# Sheet1.net
KiCad netlist of a schematic drawn in Altium Designer
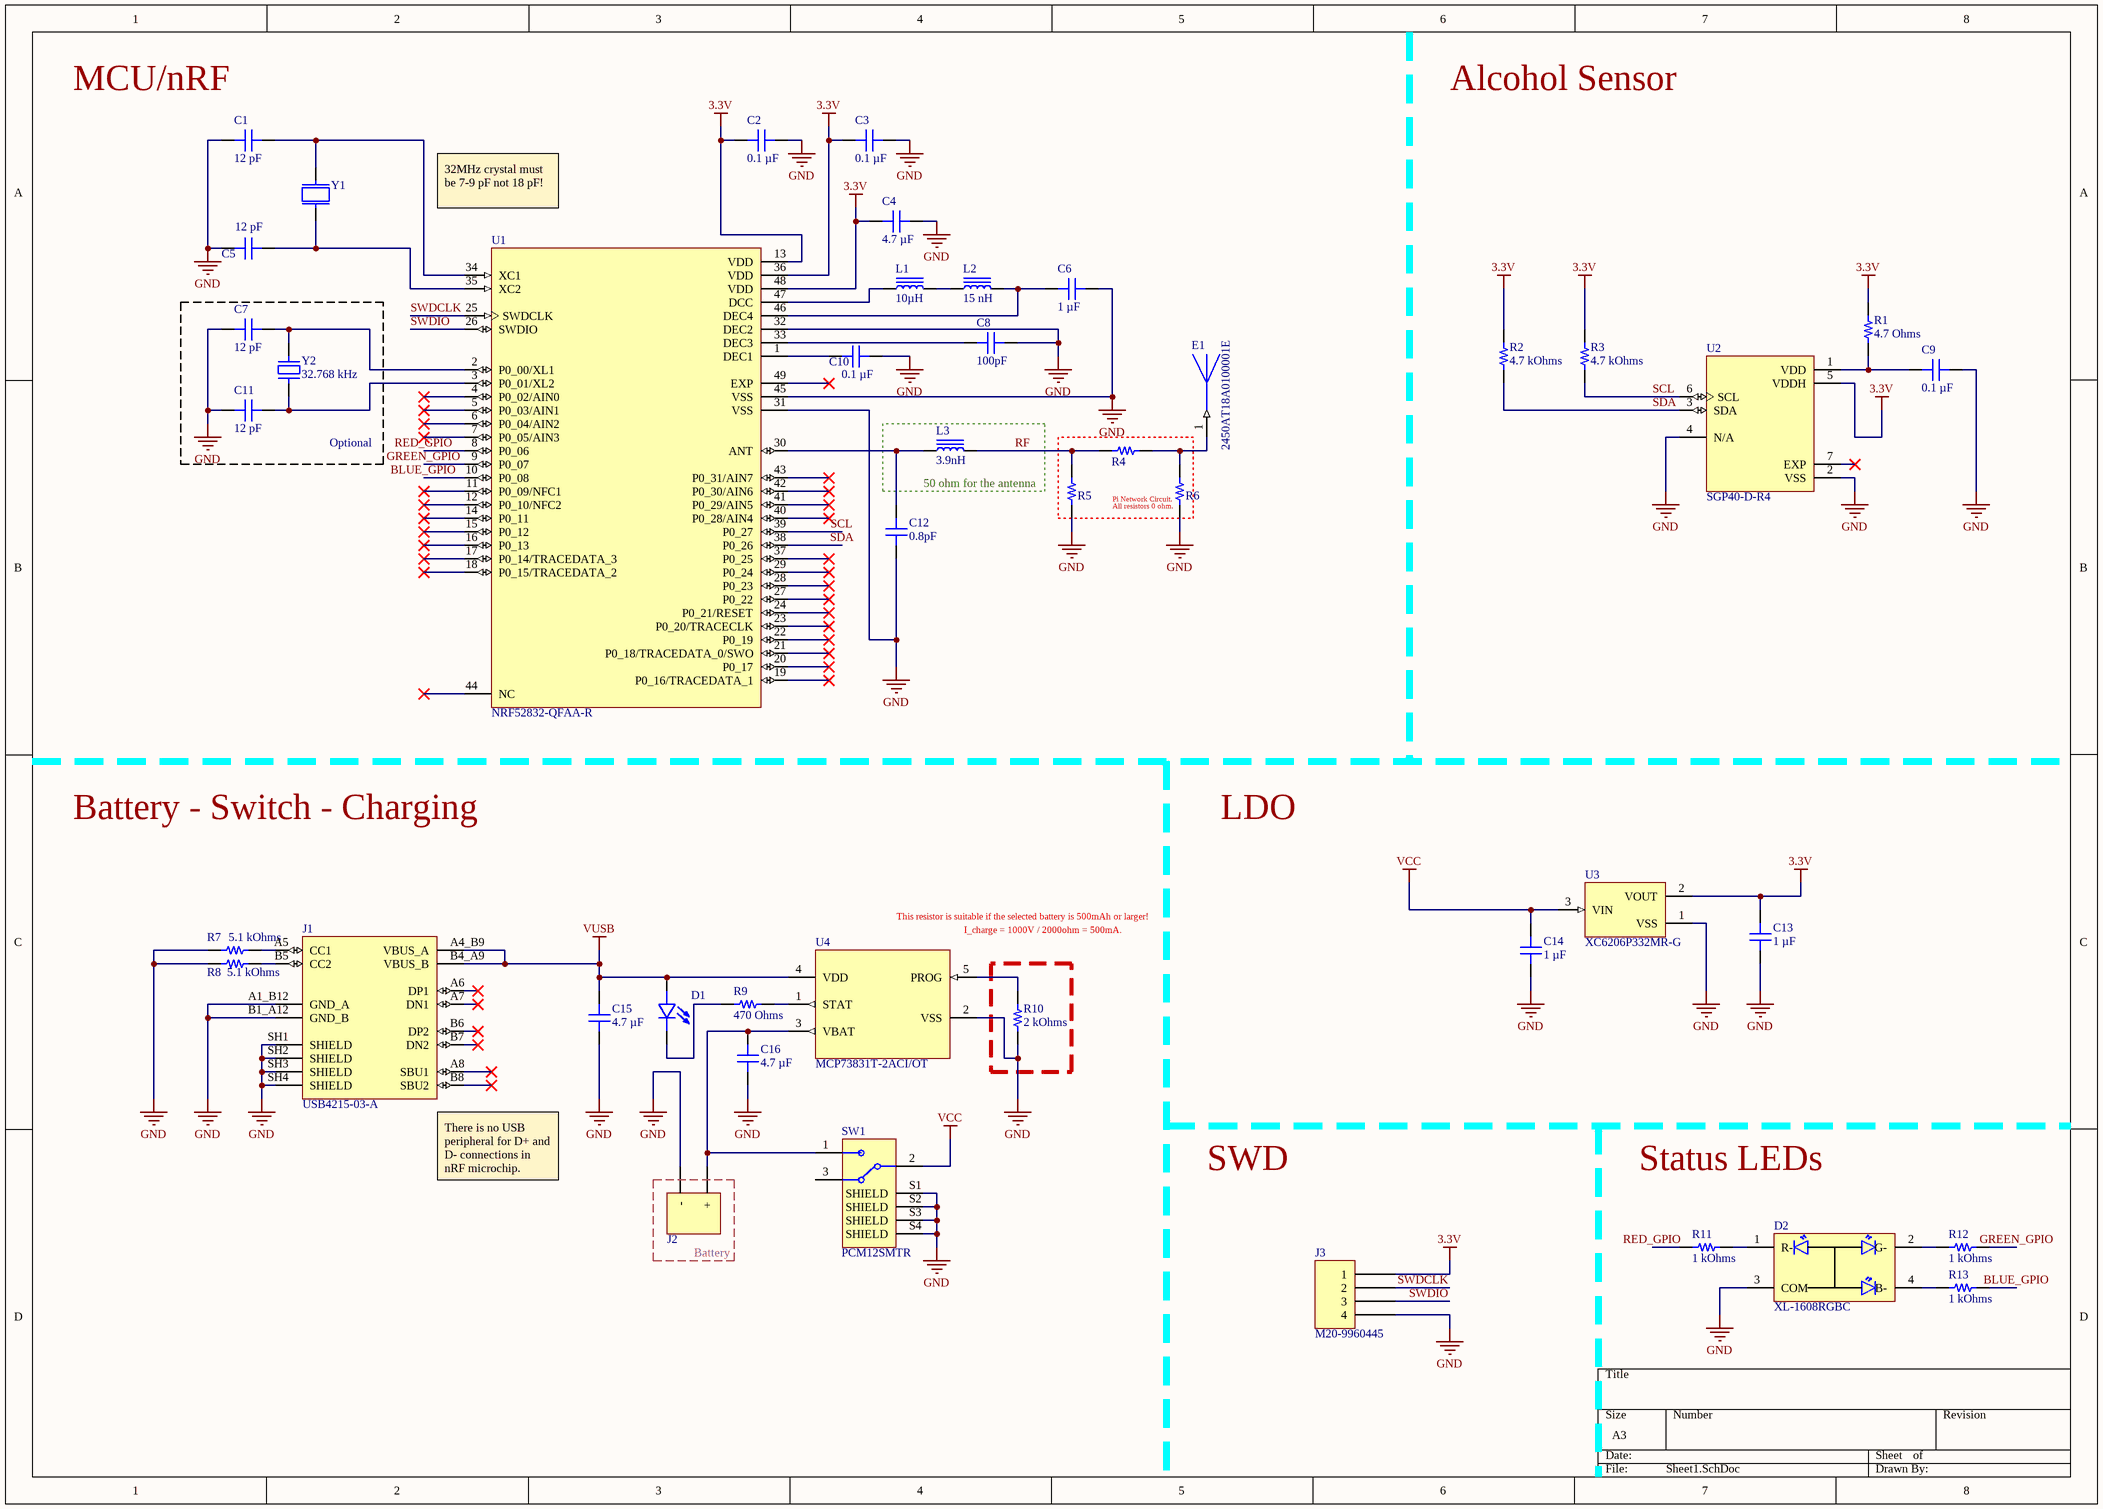
[diagram p0: Sheet1.SchDoc]

(export (version "E")
  (design (tool "Eeschema 10.0.6"))
  (components
    (comp (ref "C1")
      (value "12 pF")
      (footprint "CAP 0402_1005")
      (description "CAP CER 12PF 50V C0G/NP0 0402")
      (fields (field (name "PART NUMBER") "CBR04C120F5GAC") (field (name "MANUFACTURER") "KEMET"))
      (libsource (lib "Celestial Altium Library - altium_library") (part "Capacitor"))
    )
    (comp (ref "C2")
      (value "0.1 µF")
      (footprint "CAP 0402_1005")
      (description "CAP CER 100NF 10V X7R 0402")
      (fields
        (field (name "PART NUMBER") "CL05B104KP5VPNC")
        (field (name "MANUFACTURER") "Samsung Electro-Mechanics")
      )
      (libsource (lib "Celestial Altium Library - altium_library") (part "Capacitor"))
    )
    (comp (ref "C3")
      (value "0.1 µF")
      (footprint "CAP 0402_1005")
      (description "CAP CER 100NF 10V X7R 0402")
      (fields
        (field (name "PART NUMBER") "CL05B104KP5VPNC")
        (field (name "MANUFACTURER") "Samsung Electro-Mechanics")
      )
      (libsource (lib "Celestial Altium Library - altium_library") (part "Capacitor"))
    )
    (comp (ref "C4")
      (value "4.7 µF")
      (footprint "CAP 0402_1005")
      (description "CAP CER 4.7UF 16V X5R 0402")
      (fields
        (field (name "PART NUMBER") "CL05A475MO5NUNC")
        (field (name "MANUFACTURER") "Samsung Electro-Mechanics")
      )
      (libsource (lib "Celestial Altium Library - altium_library") (part "Capacitor"))
    )
    (comp (ref "C5")
      (value "12 pF")
      (footprint "CAP 0402_1005")
      (description "CAP CER 12PF 50V C0G/NP0 0402")
      (fields (field (name "PART NUMBER") "CBR04C120F5GAC") (field (name "MANUFACTURER") "KEMET"))
      (libsource (lib "Celestial Altium Library - altium_library") (part "Capacitor"))
    )
    (comp (ref "C6")
      (value "1 µF")
      (footprint "CAP 0402_1005")
      (description "CAP CER 1UF 10V X5R 0402")
      (fields (field (name "PART NUMBER") "885012105012") (field (name "MANUFACTURER") "Würth Elektronik"))
      (libsource (lib "Celestial Altium Library - altium_library") (part "Capacitor"))
    )
    (comp (ref "C7")
      (value "12 pF")
      (footprint "CAP 0402_1005")
      (description "CAP CER 12PF 25V NP0 0402")
      (fields (field (name "PART NUMBER") "C0402C120J3GAC7867") (field (name "MANUFACTURER") "KEMET"))
      (libsource (lib "Celestial Altium Library - altium_library") (part "Capacitor"))
    )
    (comp (ref "C8")
      (value "100pF")
      (footprint "CAP 0402_1005")
      (description "CAP CER 100PF 10V X7R 0402")
      (fields (field (name "PART NUMBER") "0402ZC101MAT2A") (field (name "MANUFACTURER") "AVX Corporation"))
      (libsource (lib "Celestial Altium Library - altium_library") (part "Capacitor"))
    )
    (comp (ref "C9")
      (value "0.1 µF")
      (footprint "CAP 0402_1005")
      (description "CAP CER 100NF 10V X7R 0402")
      (fields
        (field (name "PART NUMBER") "CL05B104KP5VPNC")
        (field (name "MANUFACTURER") "Samsung Electro-Mechanics")
      )
      (libsource (lib "Celestial Altium Library - altium_library") (part "Capacitor"))
    )
    (comp (ref "C10")
      (value "0.1 µF")
      (footprint "CAP 0402_1005")
      (description "CAP CER 100NF 10V X7R 0402")
      (fields
        (field (name "PART NUMBER") "CL05B104KP5VPNC")
        (field (name "MANUFACTURER") "Samsung Electro-Mechanics")
      )
      (libsource (lib "Celestial Altium Library - altium_library") (part "Capacitor"))
    )
    (comp (ref "C11")
      (value "12 pF")
      (footprint "CAP 0402_1005")
      (description "CAP CER 12PF 25V NP0 0402")
      (fields (field (name "PART NUMBER") "C0402C120J3GAC7867") (field (name "MANUFACTURER") "KEMET"))
      (libsource (lib "Celestial Altium Library - altium_library") (part "Capacitor"))
    )
    (comp (ref "C12")
      (value "0.8pF")
      (footprint "CAP 0402_1005")
      (description "CAP CER 0.8PF 50V NP0 0402")
      (fields (field (name "PART NUMBER") "04025A0R8BAT2A") (field (name "MANUFACTURER") "AVX Corporation"))
      (libsource (lib "Celestial Altium Library - altium_library") (part "Capacitor"))
    )
    (comp (ref "C13")
      (value "1 µF")
      (footprint "CAP 0402_1005")
      (description "CAP CER 1UF 10V X5R 0402")
      (fields (field (name "PART NUMBER") "885012105012") (field (name "MANUFACTURER") "Würth Elektronik"))
      (libsource (lib "Celestial Altium Library - altium_library") (part "Capacitor"))
    )
    (comp (ref "C14")
      (value "1 µF")
      (footprint "CAP 0402_1005")
      (description "CAP CER 1UF 10V X5R 0402")
      (fields (field (name "PART NUMBER") "885012105012") (field (name "MANUFACTURER") "Würth Elektronik"))
      (libsource (lib "Celestial Altium Library - altium_library") (part "Capacitor"))
    )
    (comp (ref "C15")
      (value "4.7 µF")
      (footprint "CAP 0402_1005")
      (description "CAP CER 4.7UF 16V X5R 0402")
      (fields
        (field (name "PART NUMBER") "CL05A475MO5NUNC")
        (field (name "MANUFACTURER") "Samsung Electro-Mechanics")
      )
      (libsource (lib "Celestial Altium Library - altium_library") (part "Capacitor"))
    )
    (comp (ref "C16")
      (value "4.7 µF")
      (footprint "CAP 0402_1005")
      (description "CAP CER 4.7UF 16V X5R 0402")
      (fields
        (field (name "PART NUMBER") "CL05A475MO5NUNC")
        (field (name "MANUFACTURER") "Samsung Electro-Mechanics")
      )
      (libsource (lib "Celestial Altium Library - altium_library") (part "Capacitor"))
    )
    (comp (ref "D1")
      (value "XZFBB53W-1")
      (footprint "XZFBB53W-1")
      (description "1.6X0.8MM BLUE SMD 0603 LED")
      (libsource (lib "Schlib1") (part "XZFBB53W-1"))
    )
    (comp (ref "D2")
      (value "XL-1608RGBC")
      (footprint "XL-1608RGBC")
      (libsource (lib "Schlib1") (part "XL-1608RGBC"))
    )
    (comp (ref "E1")
      (value "2450AT18A0100001E")
      (footprint "2450AT18A0100001E")
      (description "2.4GHz Chip RF Antenna 2.4GHz ~ 2.5GHz 0.5dBi Solder Surface Mount")
      (libsource (lib "Schlib1") (part "2450AT18A0100001E"))
    )
    (comp (ref "J1")
      (value "USB4215-03-A")
      (footprint "USB4215-03-A")
      (libsource (lib "Schlib1") (part "USB4215-03-A"))
    )
    (comp (ref "J2")
      (value "Male Header 2 Pin")
      (footprint "Male Header 2 Pin")
      (libsource (lib "Schlib1") (part "Male Header 2 Pin"))
    )
    (comp (ref "J3")
      (value "M20-9960445")
      (footprint "HARWIN M20-9960445")
      (description "CONN HEADER R/A 4POS 2.54MM")
      (fields (field (name "MANUFACTURER") "Harwin Inc."))
      (libsource (lib "Celestial Altium Library - altium_library") (part "4 Pin"))
    )
    (comp (ref "L1")
      (value "10µH")
      (footprint "IND 1008_2520")
      (description "FIXED IND 10UH 850MA 300 MOHM")
      (fields (field (name "PART NUMBER") "74479887310A") (field (name "MANUFACTURER") "Würth Elektronik"))
      (libsource (lib "Celestial Altium Library - altium_library") (part "Inductor"))
    )
    (comp (ref "L2")
      (value "15 nH")
      (footprint "IND 0201_0603")
      (description "FIXED IND 15NH 300MA 700MOHM SMD")
      (fields
        (field (name "PART NUMBER") "LQP03HQ15NJ02D")
        (field (name "MANUFACTURER") "Murata Electronics")
      )
      (libsource (lib "Celestial Altium Library - altium_library") (part "Inductor"))
    )
    (comp (ref "L3")
      (value "3.9nH")
      (footprint "IND 0402_1005")
      (description "RF INDUCTOR ML")
      (fields
        (field (name "PART NUMBER") "BSCH001005053N9SCP")
        (field (name "MANUFACTURER") "Chilisin Electronics")
      )
      (libsource (lib "Celestial Altium Library - altium_library") (part "Inductor"))
    )
    (comp (ref "R1")
      (value "4.7 Ohms")
      (footprint "RES 0402_1005")
      (description "RES SMD 4.7 OHM 5% 1/16W 0402")
      (fields (field (name "PART NUMBER") "CRCW04024R70JNED") (field (name "MANUFACTURER") "Vishay Dale"))
      (libsource (lib "Celestial Altium Library - altium_library") (part "Resistor"))
    )
    (comp (ref "R2")
      (value "4.7 kOhms")
      (footprint "RES 0402_1005")
      (description "RES SMD 4.7K OHM 0.5% 1/16W 0402")
      (fields (field (name "PART NUMBER") "RR0510P-472-D") (field (name "MANUFACTURER") "Susumu"))
      (libsource (lib "Celestial Altium Library - altium_library") (part "Resistor"))
    )
    (comp (ref "R3")
      (value "4.7 kOhms")
      (footprint "RES 0402_1005")
      (description "RES SMD 4.7K OHM 0.5% 1/16W 0402")
      (fields (field (name "PART NUMBER") "RR0510P-472-D") (field (name "MANUFACTURER") "Susumu"))
      (libsource (lib "Celestial Altium Library - altium_library") (part "Resistor"))
    )
    (comp (ref "R4")
      (value "~")
      (footprint "RES 0402_1005")
      (description "RES SMD 0 OHM JUMPER 1/10W 0402")
      (fields
        (field (name "PART NUMBER") "MCS04020Z0000ZE000")
        (field (name "MANUFACTURER") "Vishay Beyschlag")
      )
      (libsource (lib "Celestial Altium Library - altium_library") (part "Resistor"))
    )
    (comp (ref "R5")
      (value "~")
      (footprint "RES 0402_1005")
      (description "RES SMD 0 OHM JUMPER 1/10W 0402")
      (fields
        (field (name "PART NUMBER") "MCS04020Z0000ZE000")
        (field (name "MANUFACTURER") "Vishay Beyschlag")
      )
      (libsource (lib "Celestial Altium Library - altium_library") (part "Resistor"))
    )
    (comp (ref "R6")
      (value "~")
      (footprint "RES 0402_1005")
      (description "RES SMD 0 OHM JUMPER 1/10W 0402")
      (fields
        (field (name "PART NUMBER") "MCS04020Z0000ZE000")
        (field (name "MANUFACTURER") "Vishay Beyschlag")
      )
      (libsource (lib "Celestial Altium Library - altium_library") (part "Resistor"))
    )
    (comp (ref "R7")
      (value "5.1 kOhms")
      (footprint "RES 0402_1005")
      (description "RES SMD 5.1K OHM 0.1% 1/16W 0402")
      (fields
        (field (name "PART NUMBER") "ERA-2AEB512X")
        (field (name "MANUFACTURER") "Panasonic Electronic Components")
      )
      (libsource (lib "Celestial Altium Library - altium_library") (part "Resistor"))
    )
    (comp (ref "R8")
      (value "5.1 kOhms")
      (footprint "RES 0402_1005")
      (description "RES SMD 5.1K OHM 0.1% 1/16W 0402")
      (fields
        (field (name "PART NUMBER") "ERA-2AEB512X")
        (field (name "MANUFACTURER") "Panasonic Electronic Components")
      )
      (libsource (lib "Celestial Altium Library - altium_library") (part "Resistor"))
    )
    (comp (ref "R9")
      (value "470 Ohms")
      (footprint "RES 0402_1005")
      (description "RES 470 OHM 0.1% 1/16W 0402")
      (fields (field (name "PART NUMBER") "TNPW0402470RBYEP") (field (name "MANUFACTURER") "Vishay Dale"))
      (libsource (lib "Celestial Altium Library - altium_library") (part "Resistor"))
    )
    (comp (ref "R10")
      (value "2 kOhms")
      (footprint "RES 0402_1005")
      (description "RES SMD 2K OHM 0.1% 1/16W 0402")
      (fields
        (field (name "PART NUMBER") "CPF0402B2K0E1")
        (field (name "MANUFACTURER") "TE Connectivity Passive Product")
      )
      (libsource (lib "Celestial Altium Library - altium_library") (part "Resistor"))
    )
    (comp (ref "R11")
      (value "1 kOhms")
      (footprint "RES 0402_1005")
      (description "RES SMD 1K OHM 0.1% 1/16W 0402")
      (fields
        (field (name "PART NUMBER") "CPF0402B1K0E")
        (field (name "MANUFACTURER") "TE Connectivity Passive Product")
      )
      (libsource (lib "Celestial Altium Library - altium_library") (part "Resistor"))
    )
    (comp (ref "R12")
      (value "1 kOhms")
      (footprint "RES 0402_1005")
      (description "RES SMD 1K OHM 0.1% 1/16W 0402")
      (fields
        (field (name "PART NUMBER") "CPF0402B1K0E")
        (field (name "MANUFACTURER") "TE Connectivity Passive Product")
      )
      (libsource (lib "Celestial Altium Library - altium_library") (part "Resistor"))
    )
    (comp (ref "R13")
      (value "1 kOhms")
      (footprint "RES 0402_1005")
      (description "RES SMD 1K OHM 0.1% 1/16W 0402")
      (fields
        (field (name "PART NUMBER") "CPF0402B1K0E")
        (field (name "MANUFACTURER") "TE Connectivity Passive Product")
      )
      (libsource (lib "Celestial Altium Library - altium_library") (part "Resistor"))
    )
    (comp (ref "SW1")
      (value "PCM12SMTR")
      (footprint "PCM12SMTR")
      (description "Slide Switch SPDT Surface Mount, Right Angle")
      (libsource (lib "Schlib1") (part "PCM12SMTR"))
    )
    (comp (ref "U1")
      (value "NRF52832-QFAA-R")
      (footprint "NRF52832-QFAA-R")
      (description "IC RF TxRx + MCU Bluetooth, General ISM > 1GHz ANT, Bluetooth v5.0 2.4GHz 48-VFQFN Exposed Pad")
      (libsource (lib "Schlib1") (part "NRF52832-QFAA-R"))
    )
    (comp (ref "U2")
      (value "SGP40-D-R4")
      (footprint "SGP40-D-R4")
      (description "MOx based gas sensor for indoor air quality applications")
      (libsource (lib "Schlib1") (part "SGP40-D-R4"))
    )
    (comp (ref "U3")
      (value "XC6206P332MR-G")
      (footprint "SOT-23")
      (description "Linear Voltage Regulator IC Positive Fixed 1 Output 200mA SOT-23")
      (libsource (lib "Schlib1") (part "XC6206P332MR-G"))
    )
    (comp (ref "U4")
      (value "MCP73831T-2ACI/OT")
      (footprint "MCP73831T-2ACI/OT")
      (description "Charger IC Lithium Ion/Polymer SOT-23-5")
      (libsource (lib "Schlib1") (part "MCP73831T-2ACI/OT"))
    )
    (comp (ref "Y1")
      (value "XRCGB32M000F2P01R0")
      (footprint "XRCGB32M000F2P01R0")
      (description "32 MHz ±20ppm Crystal 8pF 100 Ohms 4-SMD, No Lead")
      (libsource (lib "Schlib1") (part "XRCGB32M000F2P01R0"))
    )
    (comp (ref "Y2")
      (value "32.768 kHz")
      (footprint "ABRACON ABS06")
      (description "CRYSTAL 32.7680KHZ 12.5PF SMD")
      (fields (field (name "PART NUMBER") "ABS06-32.768KHZ-1-T") (field (name "MANUFACTURER") "Abracon LLC"))
      (libsource (lib "Celestial Altium Library - altium_library") (part "Abracon Crystal ABS06"))
    )
  )
  (nets
    (net (code "1") (name "/BLUE_GPIO") (class "Default")
      (node (ref "R13") (pin "2") (pinfunction "2_2") (pintype "passive"))
      (node (ref "U1") (pin "10") (pinfunction "P0_08_10") (pintype "bidirectional"))
    )
    (net (code "2") (name "/GREEN_GPIO") (class "Default")
      (node (ref "R12") (pin "2") (pinfunction "2_2") (pintype "passive"))
      (node (ref "U1") (pin "9") (pinfunction "P0_07_9") (pintype "bidirectional"))
    )
    (net (code "3") (name "/RED_GPIO") (class "Default")
      (node (ref "R11") (pin "1") (pinfunction "1_1") (pintype "passive"))
      (node (ref "U1") (pin "8") (pinfunction "P0_06_8") (pintype "bidirectional"))
    )
    (net (code "4") (name "/RF") (class "Default")
      (node (ref "L3") (pin "2") (pinfunction "2_2") (pintype "passive"))
      (node (ref "R4") (pin "1") (pinfunction "1_1") (pintype "passive"))
      (node (ref "R5") (pin "1") (pinfunction "1_1") (pintype "passive"))
    )
    (net (code "5") (name "/SCL") (class "Default")
      (node (ref "R3") (pin "1") (pinfunction "1_1") (pintype "passive"))
      (node (ref "U1") (pin "39") (pinfunction "P0_27_39") (pintype "bidirectional"))
      (node (ref "U2") (pin "6") (pinfunction "SCL_6") (pintype "bidirectional"))
    )
    (net (code "6") (name "/SDA") (class "Default")
      (node (ref "R2") (pin "1") (pinfunction "1_1") (pintype "passive"))
      (node (ref "U1") (pin "38") (pinfunction "P0_26_38") (pintype "bidirectional"))
      (node (ref "U2") (pin "3") (pinfunction "SDA_3") (pintype "bidirectional"))
    )
    (net (code "7") (name "/SWDCLK") (class "Default")
      (node (ref "J3") (pin "2") (pinfunction "2_2") (pintype "passive"))
      (node (ref "U1") (pin "25") (pinfunction "SWDCLK_25") (pintype "input"))
    )
    (net (code "8") (name "/SWDIO") (class "Default")
      (node (ref "J3") (pin "3") (pinfunction "3_3") (pintype "passive"))
      (node (ref "U1") (pin "26") (pinfunction "SWDIO_26") (pintype "bidirectional"))
    )
    (net (code "9") (name "3.3V") (class "Default")
      (node (ref "C13") (pin "2") (pinfunction "2_2") (pintype "passive"))
      (node (ref "C2") (pin "1") (pinfunction "1_1") (pintype "passive"))
      (node (ref "C3") (pin "1") (pinfunction "1_1") (pintype "passive"))
      (node (ref "C4") (pin "1") (pinfunction "1_1") (pintype "passive"))
      (node (ref "J3") (pin "1") (pinfunction "1_1") (pintype "passive"))
      (node (ref "R1") (pin "2") (pinfunction "2_2") (pintype "passive"))
      (node (ref "R2") (pin "2") (pinfunction "2_2") (pintype "passive"))
      (node (ref "R3") (pin "2") (pinfunction "2_2") (pintype "passive"))
      (node (ref "U1") (pin "13") (pinfunction "VDD_13") (pintype "power_in"))
      (node (ref "U1") (pin "36") (pinfunction "VDD_36") (pintype "power_in"))
      (node (ref "U1") (pin "48") (pinfunction "VDD_48") (pintype "power_in"))
      (node (ref "U2") (pin "5") (pinfunction "VDDH_5") (pintype "power_in"))
      (node (ref "U3") (pin "2") (pinfunction "VOUT_2") (pintype "power_in"))
    )
    (net (code "10") (name "GND") (class "Default")
      (node (ref "C1") (pin "1") (pinfunction "1_1") (pintype "passive"))
      (node (ref "C10") (pin "1") (pinfunction "1_1") (pintype "passive"))
      (node (ref "C11") (pin "1") (pinfunction "1_1") (pintype "passive"))
      (node (ref "C12") (pin "1") (pinfunction "1_1") (pintype "passive"))
      (node (ref "C13") (pin "1") (pinfunction "1_1") (pintype "passive"))
      (node (ref "C14") (pin "1") (pinfunction "1_1") (pintype "passive"))
      (node (ref "C15") (pin "1") (pinfunction "1_1") (pintype "passive"))
      (node (ref "C16") (pin "1") (pinfunction "1_1") (pintype "passive"))
      (node (ref "C2") (pin "2") (pinfunction "2_2") (pintype "passive"))
      (node (ref "C3") (pin "2") (pinfunction "2_2") (pintype "passive"))
      (node (ref "C4") (pin "2") (pinfunction "2_2") (pintype "passive"))
      (node (ref "C5") (pin "2") (pinfunction "2_2") (pintype "passive"))
      (node (ref "C6") (pin "1") (pinfunction "1_1") (pintype "passive"))
      (node (ref "C7") (pin "1") (pinfunction "1_1") (pintype "passive"))
      (node (ref "C8") (pin "2") (pinfunction "2_2") (pintype "passive"))
      (node (ref "C9") (pin "2") (pinfunction "2_2") (pintype "passive"))
      (node (ref "D2") (pin "3") (pinfunction "COM_3") (pintype "passive"))
      (node (ref "J1") (pin "A1_B12") (pinfunction "GND_A_A1_B12") (pintype "power_in"))
      (node (ref "J1") (pin "B1_A12") (pinfunction "GND_B_B1_A12") (pintype "power_in"))
      (node (ref "J1") (pin "SH1") (pinfunction "SHIELD_SH1") (pintype "passive"))
      (node (ref "J1") (pin "SH2") (pinfunction "SHIELD_SH2") (pintype "passive"))
      (node (ref "J1") (pin "SH3") (pinfunction "SHIELD_SH3") (pintype "passive"))
      (node (ref "J1") (pin "SH4") (pinfunction "SHIELD_SH4") (pintype "passive"))
      (node (ref "J2") (pin "01") (pinfunction "-_01") (pintype "passive"))
      (node (ref "J3") (pin "4") (pinfunction "4_4") (pintype "passive"))
      (node (ref "R10") (pin "1") (pinfunction "1_1") (pintype "passive"))
      (node (ref "R5") (pin "2") (pinfunction "2_2") (pintype "passive"))
      (node (ref "R6") (pin "2") (pinfunction "2_2") (pintype "passive"))
      (node (ref "R7") (pin "1") (pinfunction "1_1") (pintype "passive"))
      (node (ref "R8") (pin "1") (pinfunction "1_1") (pintype "passive"))
      (node (ref "SW1") (pin "S1") (pinfunction "SHIELD_S1") (pintype "passive"))
      (node (ref "SW1") (pin "S2") (pinfunction "SHIELD_S2") (pintype "passive"))
      (node (ref "SW1") (pin "S3") (pinfunction "SHIELD_S3") (pintype "passive"))
      (node (ref "SW1") (pin "S4") (pinfunction "SHIELD_S4") (pintype "passive"))
      (node (ref "U1") (pin "31") (pinfunction "VSS_31") (pintype "power_in"))
      (node (ref "U1") (pin "32") (pinfunction "DEC2_32") (pintype "power_in"))
      (node (ref "U1") (pin "45") (pinfunction "VSS_45") (pintype "power_in"))
      (node (ref "U2") (pin "2") (pinfunction "VSS_2") (pintype "power_in"))
      (node (ref "U2") (pin "4") (pinfunction "N/A_4") (pintype "passive"))
      (node (ref "U3") (pin "1") (pinfunction "VSS_1") (pintype "passive"))
      (node (ref "U4") (pin "2") (pinfunction "VSS_2") (pintype "power_in"))
    )
    (net (code "11") (name "Net-(D1-PadC)") (class "Default")
      (node (ref "D1") (pin "C") (pinfunction "C_C") (pintype "passive"))
      (node (ref "R9") (pin "1") (pinfunction "1_1") (pintype "passive"))
    )
    (net (code "12") (name "Net-(D2-B-)") (class "Default")
      (node (ref "D2") (pin "4") (pinfunction "B-_4") (pintype "passive"))
      (node (ref "R13") (pin "1") (pinfunction "1_1") (pintype "passive"))
    )
    (net (code "13") (name "Net-(D2-G-)") (class "Default")
      (node (ref "D2") (pin "2") (pinfunction "G-_2") (pintype "passive"))
      (node (ref "R12") (pin "1") (pinfunction "1_1") (pintype "passive"))
    )
    (net (code "14") (name "Net-(D2-R-)") (class "Default")
      (node (ref "D2") (pin "1") (pinfunction "R-_1") (pintype "passive"))
      (node (ref "R11") (pin "2") (pinfunction "2_2") (pintype "passive"))
    )
    (net (code "15") (name "Net-(E1-Pad1)") (class "Default")
      (node (ref "E1") (pin "1") (pinfunction "1_1") (pintype "input"))
      (node (ref "R4") (pin "2") (pinfunction "2_2") (pintype "passive"))
      (node (ref "R6") (pin "1") (pinfunction "1_1") (pintype "passive"))
    )
    (net (code "16") (name "Net-(J1-CC1)") (class "Default")
      (node (ref "J1") (pin "A5") (pinfunction "CC1_A5") (pintype "bidirectional"))
      (node (ref "R7") (pin "2") (pinfunction "2_2") (pintype "passive"))
    )
    (net (code "17") (name "Net-(J1-CC2)") (class "Default")
      (node (ref "J1") (pin "B5") (pinfunction "CC2_B5") (pintype "bidirectional"))
      (node (ref "R8") (pin "2") (pinfunction "2_2") (pintype "passive"))
    )
    (net (code "18") (name "Net-(J2-+)") (class "Default")
      (node (ref "C16") (pin "2") (pinfunction "2_2") (pintype "passive"))
      (node (ref "J2") (pin "02") (pinfunction "+_02") (pintype "passive"))
      (node (ref "SW1") (pin "1") (pinfunction "1_1") (pintype "passive"))
      (node (ref "U4") (pin "3") (pinfunction "VBAT_3") (pintype "output"))
    )
    (net (code "19") (name "Net-(L1-Pad2)") (class "Default")
      (node (ref "L1") (pin "2") (pinfunction "2_2") (pintype "passive"))
      (node (ref "L2") (pin "1") (pinfunction "1_1") (pintype "passive"))
    )
    (net (code "20") (name "Net-(U1-ANT)") (class "Default")
      (node (ref "C12") (pin "2") (pinfunction "2_2") (pintype "passive"))
      (node (ref "L3") (pin "1") (pinfunction "1_1") (pintype "passive"))
      (node (ref "U1") (pin "30") (pinfunction "ANT_30") (pintype "bidirectional"))
    )
    (net (code "21") (name "Net-(U1-DCC)") (class "Default")
      (node (ref "L1") (pin "1") (pinfunction "1_1") (pintype "passive"))
      (node (ref "U1") (pin "47") (pinfunction "DCC_47") (pintype "power_in"))
    )
    (net (code "22") (name "Net-(U1-DEC1)") (class "Default")
      (node (ref "C10") (pin "2") (pinfunction "2_2") (pintype "passive"))
      (node (ref "U1") (pin "1") (pinfunction "DEC1_1") (pintype "power_in"))
    )
    (net (code "23") (name "Net-(U1-DEC3)") (class "Default")
      (node (ref "C8") (pin "1") (pinfunction "1_1") (pintype "passive"))
      (node (ref "U1") (pin "33") (pinfunction "DEC3_33") (pintype "power_in"))
    )
    (net (code "24") (name "Net-(U1-DEC4)") (class "Default")
      (node (ref "C6") (pin "2") (pinfunction "2_2") (pintype "passive"))
      (node (ref "L2") (pin "2") (pinfunction "2_2") (pintype "passive"))
      (node (ref "U1") (pin "46") (pinfunction "DEC4_46") (pintype "power_in"))
    )
    (net (code "25") (name "Net-(U1-P0_00{slash}XL1)") (class "Default")
      (node (ref "C7") (pin "2") (pinfunction "2_2") (pintype "passive"))
      (node (ref "U1") (pin "2") (pinfunction "P0_00/XL1_2") (pintype "bidirectional"))
      (node (ref "Y2") (pin "2") (pinfunction "2_2") (pintype "passive"))
    )
    (net (code "26") (name "Net-(U1-P0_01{slash}XL2)") (class "Default")
      (node (ref "C11") (pin "2") (pinfunction "2_2") (pintype "passive"))
      (node (ref "U1") (pin "3") (pinfunction "P0_01/XL2_3") (pintype "bidirectional"))
      (node (ref "Y2") (pin "1") (pinfunction "1_1") (pintype "passive"))
    )
    (net (code "27") (name "Net-(U1-XC1)") (class "Default")
      (node (ref "C1") (pin "2") (pinfunction "2_2") (pintype "passive"))
      (node (ref "U1") (pin "34") (pinfunction "XC1_34") (pintype "input"))
      (node (ref "Y1") (pin "2") (pinfunction "2_2") (pintype "passive"))
    )
    (net (code "28") (name "Net-(U1-XC2)") (class "Default")
      (node (ref "C5") (pin "1") (pinfunction "1_1") (pintype "passive"))
      (node (ref "U1") (pin "35") (pinfunction "XC2_35") (pintype "input"))
      (node (ref "Y1") (pin "1") (pinfunction "1_1") (pintype "passive"))
    )
    (net (code "29") (name "Net-(U2-VDD)") (class "Default")
      (node (ref "C9") (pin "1") (pinfunction "1_1") (pintype "passive"))
      (node (ref "R1") (pin "1") (pinfunction "1_1") (pintype "passive"))
      (node (ref "U2") (pin "1") (pinfunction "VDD_1") (pintype "power_in"))
    )
    (net (code "30") (name "Net-(U4-PROG)") (class "Default")
      (node (ref "R10") (pin "2") (pinfunction "2_2") (pintype "passive"))
      (node (ref "U4") (pin "5") (pinfunction "PROG_5") (pintype "input"))
    )
    (net (code "31") (name "Net-(U4-STAT)") (class "Default")
      (node (ref "R9") (pin "2") (pinfunction "2_2") (pintype "passive"))
      (node (ref "U4") (pin "1") (pinfunction "STAT_1") (pintype "output"))
    )
    (net (code "32") (name "VCC") (class "Default")
      (node (ref "C14") (pin "2") (pinfunction "2_2") (pintype "passive"))
      (node (ref "SW1") (pin "2") (pinfunction "2_2") (pintype "passive"))
      (node (ref "U3") (pin "3") (pinfunction "VIN_3") (pintype "input"))
    )
    (net (code "33") (name "VUSB") (class "Default")
      (node (ref "C15") (pin "2") (pinfunction "2_2") (pintype "passive"))
      (node (ref "D1") (pin "A") (pinfunction "A_A") (pintype "passive"))
      (node (ref "J1") (pin "A4_B9") (pinfunction "VBUS_A_A4_B9") (pintype "power_in"))
      (node (ref "J1") (pin "B4_A9") (pinfunction "VBUS_B_B4_A9") (pintype "power_in"))
      (node (ref "U4") (pin "4") (pinfunction "VDD_4") (pintype "power_in"))
    )
    (net (code "34") (name "unconnected-(J1-DN1-PadA7)") (class "Default")
      (node (ref "J1") (pin "A7") (pinfunction "DN1_A7") (pintype "bidirectional+no_connect"))
    )
    (net (code "35") (name "unconnected-(J1-DN2-PadB7)") (class "Default")
      (node (ref "J1") (pin "B7") (pinfunction "DN2_B7") (pintype "bidirectional+no_connect"))
    )
    (net (code "36") (name "unconnected-(J1-DP1-PadA6)") (class "Default")
      (node (ref "J1") (pin "A6") (pinfunction "DP1_A6") (pintype "bidirectional+no_connect"))
    )
    (net (code "37") (name "unconnected-(J1-DP2-PadB6)") (class "Default")
      (node (ref "J1") (pin "B6") (pinfunction "DP2_B6") (pintype "bidirectional+no_connect"))
    )
    (net (code "38") (name "unconnected-(J1-SBU1-PadA8)") (class "Default")
      (node (ref "J1") (pin "A8") (pinfunction "SBU1_A8") (pintype "bidirectional+no_connect"))
    )
    (net (code "39") (name "unconnected-(J1-SBU2-PadB8)") (class "Default")
      (node (ref "J1") (pin "B8") (pinfunction "SBU2_B8") (pintype "bidirectional+no_connect"))
    )
    (net (code "40") (name "unconnected-(SW1-Pad3)") (class "Default")
      (node (ref "SW1") (pin "3") (pinfunction "3_3") (pintype "passive"))
    )
    (net (code "41") (name "unconnected-(U1-EXP-Pad49)") (class "Default")
      (node (ref "U1") (pin "49") (pinfunction "EXP_49") (pintype "power_in+no_connect"))
    )
    (net (code "42") (name "unconnected-(U1-NC-Pad44)") (class "Default")
      (node (ref "U1") (pin "44") (pinfunction "NC_44") (pintype "passive+no_connect"))
    )
    (net (code "43") (name "unconnected-(U1-P0_02{slash}AIN0-Pad4)") (class "Default")
      (node (ref "U1") (pin "4") (pinfunction "P0_02/AIN0_4") (pintype "bidirectional+no_connect"))
    )
    (net (code "44") (name "unconnected-(U1-P0_03{slash}AIN1-Pad5)") (class "Default")
      (node (ref "U1") (pin "5") (pinfunction "P0_03/AIN1_5") (pintype "bidirectional+no_connect"))
    )
    (net (code "45") (name "unconnected-(U1-P0_04{slash}AIN2-Pad6)") (class "Default")
      (node (ref "U1") (pin "6") (pinfunction "P0_04/AIN2_6") (pintype "bidirectional+no_connect"))
    )
    (net (code "46") (name "unconnected-(U1-P0_05{slash}AIN3-Pad7)") (class "Default")
      (node (ref "U1") (pin "7") (pinfunction "P0_05/AIN3_7") (pintype "bidirectional+no_connect"))
    )
    (net (code "47") (name "unconnected-(U1-P0_09{slash}NFC1-Pad11)") (class "Default")
      (node (ref "U1") (pin "11") (pinfunction "P0_09/NFC1_11") (pintype "bidirectional+no_connect"))
    )
    (net (code "48") (name "unconnected-(U1-P0_10{slash}NFC2-Pad12)") (class "Default")
      (node (ref "U1") (pin "12") (pinfunction "P0_10/NFC2_12") (pintype "bidirectional+no_connect"))
    )
    (net (code "49") (name "unconnected-(U1-P0_11-Pad14)") (class "Default")
      (node (ref "U1") (pin "14") (pinfunction "P0_11_14") (pintype "bidirectional+no_connect"))
    )
    (net (code "50") (name "unconnected-(U1-P0_12-Pad15)") (class "Default")
      (node (ref "U1") (pin "15") (pinfunction "P0_12_15") (pintype "bidirectional+no_connect"))
    )
    (net (code "51") (name "unconnected-(U1-P0_13-Pad16)") (class "Default")
      (node (ref "U1") (pin "16") (pinfunction "P0_13_16") (pintype "bidirectional+no_connect"))
    )
    (net (code "52") (name "unconnected-(U1-P0_14{slash}TRACEDATA_3-Pad17)") (class "Default")
      (node (ref "U1") (pin "17") (pinfunction "P0_14/TRACEDATA_3_17") (pintype "bidirectional+no_connect"))
    )
    (net (code "53") (name "unconnected-(U1-P0_15{slash}TRACEDATA_2-Pad18)") (class "Default")
      (node (ref "U1") (pin "18") (pinfunction "P0_15/TRACEDATA_2_18") (pintype "bidirectional+no_connect"))
    )
    (net (code "54") (name "unconnected-(U1-P0_16{slash}TRACEDATA_1-Pad19)") (class "Default")
      (node (ref "U1") (pin "19") (pinfunction "P0_16/TRACEDATA_1_19") (pintype "bidirectional+no_connect"))
    )
    (net (code "55") (name "unconnected-(U1-P0_17-Pad20)") (class "Default")
      (node (ref "U1") (pin "20") (pinfunction "P0_17_20") (pintype "bidirectional+no_connect"))
    )
    (net (code "56") (name "unconnected-(U1-P0_18{slash}TRACEDATA_0{slash}SWO-Pad21)") (class "Default")
      (node (ref "U1") (pin "21") (pinfunction "P0_18/TRACEDATA_0/SWO_21") (pintype "bidirectional+no_connect"))
    )
    (net (code "57") (name "unconnected-(U1-P0_19-Pad22)") (class "Default")
      (node (ref "U1") (pin "22") (pinfunction "P0_19_22") (pintype "bidirectional+no_connect"))
    )
    (net (code "58") (name "unconnected-(U1-P0_20{slash}TRACECLK-Pad23)") (class "Default")
      (node (ref "U1") (pin "23") (pinfunction "P0_20/TRACECLK_23") (pintype "bidirectional+no_connect"))
    )
    (net (code "59") (name "unconnected-(U1-P0_21{slash}RESET-Pad24)") (class "Default")
      (node (ref "U1") (pin "24") (pinfunction "P0_21/RESET_24") (pintype "bidirectional+no_connect"))
    )
    (net (code "60") (name "unconnected-(U1-P0_22-Pad27)") (class "Default")
      (node (ref "U1") (pin "27") (pinfunction "P0_22_27") (pintype "bidirectional+no_connect"))
    )
    (net (code "61") (name "unconnected-(U1-P0_23-Pad28)") (class "Default")
      (node (ref "U1") (pin "28") (pinfunction "P0_23_28") (pintype "bidirectional+no_connect"))
    )
    (net (code "62") (name "unconnected-(U1-P0_24-Pad29)") (class "Default")
      (node (ref "U1") (pin "29") (pinfunction "P0_24_29") (pintype "bidirectional+no_connect"))
    )
    (net (code "63") (name "unconnected-(U1-P0_25-Pad37)") (class "Default")
      (node (ref "U1") (pin "37") (pinfunction "P0_25_37") (pintype "bidirectional+no_connect"))
    )
    (net (code "64") (name "unconnected-(U1-P0_28{slash}AIN4-Pad40)") (class "Default")
      (node (ref "U1") (pin "40") (pinfunction "P0_28/AIN4_40") (pintype "bidirectional+no_connect"))
    )
    (net (code "65") (name "unconnected-(U1-P0_29{slash}AIN5-Pad41)") (class "Default")
      (node (ref "U1") (pin "41") (pinfunction "P0_29/AIN5_41") (pintype "bidirectional+no_connect"))
    )
    (net (code "66") (name "unconnected-(U1-P0_30{slash}AIN6-Pad42)") (class "Default")
      (node (ref "U1") (pin "42") (pinfunction "P0_30/AIN6_42") (pintype "bidirectional+no_connect"))
    )
    (net (code "67") (name "unconnected-(U1-P0_31{slash}AIN7-Pad43)") (class "Default")
      (node (ref "U1") (pin "43") (pinfunction "P0_31/AIN7_43") (pintype "bidirectional+no_connect"))
    )
    (net (code "68") (name "unconnected-(U2-EXP-Pad7)") (class "Default")
      (node (ref "U2") (pin "7") (pinfunction "EXP_7") (pintype "power_in+no_connect"))
    )
  )
)
